# roomba.net
KiCad netlist of a schematic drawn in EAGLE
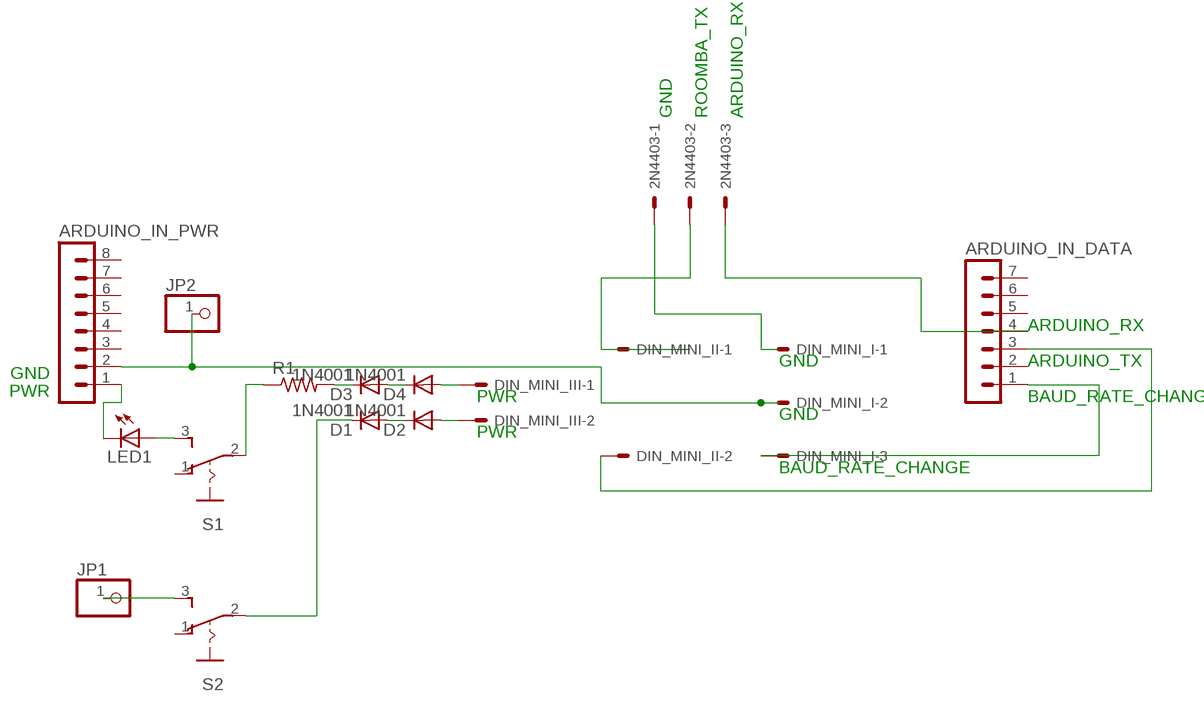
[diagram p0: schematic, sheet 1]

(export (version "E")
  (design (tool "Eeschema 10.0.6"))
  (components
    (comp (ref "2N4403")
      (value "22-23-2031")
      (footprint "eagle-import:22-23-2031")
      (fields (field (name "MF") "MOLEX"))
      (libsource (lib "eagle-import") (part "22-23-2031"))
    )
    (comp (ref "ARDUINO_IN_DATA")
      (value "MA07-1")
      (footprint "eagle-import:MA07-1")
      (libsource (lib "eagle-import") (part "MA07-1"))
    )
    (comp (ref "ARDUINO_IN_PWR")
      (value "MA08-1")
      (footprint "eagle-import:MA08-1")
      (libsource (lib "eagle-import") (part "MA08-1"))
    )
    (comp (ref "D1")
      (value "1N4001")
      (footprint "eagle-import:DO41-10")
      (libsource (lib "eagle-import") (part "1N4004"))
    )
    (comp (ref "D2")
      (value "1N4001")
      (footprint "eagle-import:DO41-10")
      (libsource (lib "eagle-import") (part "1N4004"))
    )
    (comp (ref "D3")
      (value "1N4001")
      (footprint "eagle-import:DO41-10")
      (libsource (lib "eagle-import") (part "1N4004"))
    )
    (comp (ref "D4")
      (value "1N4001")
      (footprint "eagle-import:DO41-10")
      (libsource (lib "eagle-import") (part "1N4004"))
    )
    (comp (ref "DIN_MINI_I")
      (value "22-23-2031")
      (footprint "eagle-import:22-23-2031")
      (fields (field (name "MF") "MOLEX"))
      (libsource (lib "eagle-import") (part "22-23-2031"))
    )
    (comp (ref "DIN_MINI_II")
      (value "22-23-2021")
      (footprint "eagle-import:22-23-2021")
      (fields (field (name "MF") "MOLEX"))
      (libsource (lib "eagle-import") (part "22-23-2021"))
    )
    (comp (ref "DIN_MINI_III")
      (value "22-23-2021")
      (footprint "eagle-import:22-23-2021")
      (fields (field (name "MF") "MOLEX"))
      (libsource (lib "eagle-import") (part "22-23-2021"))
    )
    (comp (ref "JP1")
      (value "PINHD-1X1")
      (footprint "eagle-import:1X01")
      (libsource (lib "eagle-import") (part "PINHD-1X1"))
    )
    (comp (ref "JP2")
      (value "PINHD-1X1")
      (footprint "eagle-import:1X01")
      (libsource (lib "eagle-import") (part "PINHD-1X1"))
    )
    (comp (ref "LED1")
      (value "LED5MM")
      (footprint "eagle-import:LED5MM")
      (libsource (lib "eagle-import") (part "LED5MM"))
    )
    (comp (ref "R1")
      (value "R-US_0207/7")
      (footprint "eagle-import:0207_7")
      (libsource (lib "eagle-import") (part "R-US_0207/7"))
    )
    (comp (ref "S1")
      (value "M251")
      (footprint "eagle-import:M251")
      (libsource (lib "eagle-import") (part "M251"))
    )
    (comp (ref "S2")
      (value "M251")
      (footprint "eagle-import:M251")
      (libsource (lib "eagle-import") (part "M251"))
    )
  )
  (nets
    (net (code "1") (name "Net-(2N4403A-S)") (class "Default")
      (node (ref "2N4403") (pin "1") (pinfunction "S_1") (pintype "passive"))
      (node (ref "DIN_MINI_I") (pin "1") (pinfunction "S_1") (pintype "passive"))
    )
    (net (code "2") (name "Net-(2N4403B-S)") (class "Default")
      (node (ref "2N4403") (pin "2") (pinfunction "S_2") (pintype "passive"))
      (node (ref "DIN_MINI_II") (pin "1") (pinfunction "S_1") (pintype "passive"))
    )
    (net (code "3") (name "Net-(2N4403C-S)") (class "Default")
      (node (ref "2N4403") (pin "3") (pinfunction "S_3") (pintype "passive"))
      (node (ref "ARDUINO_IN_DATA") (pin "4") (pinfunction "4_4") (pintype "passive"))
    )
    (net (code "4") (name "Net-(D1-PadA)") (class "Default")
      (node (ref "D1") (pin "A") (pinfunction "A_A") (pintype "passive"))
      (node (ref "D2") (pin "C") (pinfunction "C_C") (pintype "passive"))
    )
    (net (code "5") (name "Net-(D3-PadA)") (class "Default")
      (node (ref "D3") (pin "A") (pinfunction "A_A") (pintype "passive"))
      (node (ref "D4") (pin "C") (pinfunction "C_C") (pintype "passive"))
    )
    (net (code "6") (name "Net-(D3-PadC)") (class "Default")
      (node (ref "D3") (pin "C") (pinfunction "C_C") (pintype "passive"))
      (node (ref "R1") (pin "2") (pinfunction "2_2") (pintype "passive"))
    )
    (net (code "7") (name "Net-(DIN_MINI_IB-S)") (class "Default")
      (node (ref "ARDUINO_IN_PWR") (pin "2") (pinfunction "2_2") (pintype "passive"))
      (node (ref "DIN_MINI_I") (pin "2") (pinfunction "S_2") (pintype "passive"))
      (node (ref "JP2") (pin "1") (pinfunction "1_1") (pintype "passive"))
    )
    (net (code "8") (name "Net-(DIN_MINI_IC-S)") (class "Default")
      (node (ref "ARDUINO_IN_DATA") (pin "1") (pinfunction "1_1") (pintype "passive"))
      (node (ref "DIN_MINI_I") (pin "3") (pinfunction "S_3") (pintype "passive"))
    )
    (net (code "9") (name "Net-(DIN_MINI_IIB-S)") (class "Default")
      (node (ref "ARDUINO_IN_DATA") (pin "3") (pinfunction "3_3") (pintype "passive"))
      (node (ref "DIN_MINI_II") (pin "2") (pinfunction "S_2") (pintype "passive"))
    )
    (net (code "10") (name "Net-(DIN_MINI_IIIA-S)") (class "Default")
      (node (ref "D4") (pin "A") (pinfunction "A_A") (pintype "passive"))
      (node (ref "DIN_MINI_III") (pin "1") (pinfunction "S_1") (pintype "passive"))
    )
    (net (code "11") (name "Net-(DIN_MINI_IIIB-S)") (class "Default")
      (node (ref "D2") (pin "A") (pinfunction "A_A") (pintype "passive"))
      (node (ref "DIN_MINI_III") (pin "2") (pinfunction "S_2") (pintype "passive"))
    )
    (net (code "12") (name "Net-(LED1-C)") (class "Default")
      (node (ref "ARDUINO_IN_PWR") (pin "1") (pinfunction "1_1") (pintype "passive"))
      (node (ref "LED1") (pin "K") (pinfunction "C_K") (pintype "passive"))
    )
    (net (code "13") (name "Net-(S1-P)") (class "Default")
      (node (ref "R1") (pin "1") (pinfunction "1_1") (pintype "passive"))
      (node (ref "S1") (pin "2") (pinfunction "P_2") (pintype "passive"))
    )
    (net (code "14") (name "Net-(S1-S)") (class "Default")
      (node (ref "LED1") (pin "A") (pinfunction "A_A") (pintype "passive"))
      (node (ref "S1") (pin "3") (pinfunction "S_3") (pintype "passive"))
    )
    (net (code "15") (name "Net-(S2-P)") (class "Default")
      (node (ref "D1") (pin "C") (pinfunction "C_C") (pintype "passive"))
      (node (ref "S2") (pin "2") (pinfunction "P_2") (pintype "passive"))
    )
    (net (code "16") (name "Net-(S2-S)") (class "Default")
      (node (ref "JP1") (pin "1") (pinfunction "1_1") (pintype "passive"))
      (node (ref "S2") (pin "3") (pinfunction "S_3") (pintype "passive"))
    )
    (net (code "17") (name "unconnected-(ARDUINO_IN_DATA-Pad2)") (class "Default")
      (node (ref "ARDUINO_IN_DATA") (pin "2") (pinfunction "2_2") (pintype "passive"))
    )
    (net (code "18") (name "unconnected-(ARDUINO_IN_DATA-Pad5)") (class "Default")
      (node (ref "ARDUINO_IN_DATA") (pin "5") (pinfunction "5_5") (pintype "passive"))
    )
    (net (code "19") (name "unconnected-(ARDUINO_IN_DATA-Pad6)") (class "Default")
      (node (ref "ARDUINO_IN_DATA") (pin "6") (pinfunction "6_6") (pintype "passive"))
    )
    (net (code "20") (name "unconnected-(ARDUINO_IN_DATA-Pad7)") (class "Default")
      (node (ref "ARDUINO_IN_DATA") (pin "7") (pinfunction "7_7") (pintype "passive"))
    )
    (net (code "21") (name "unconnected-(ARDUINO_IN_PWR-Pad3)") (class "Default")
      (node (ref "ARDUINO_IN_PWR") (pin "3") (pinfunction "3_3") (pintype "passive"))
    )
    (net (code "22") (name "unconnected-(ARDUINO_IN_PWR-Pad4)") (class "Default")
      (node (ref "ARDUINO_IN_PWR") (pin "4") (pinfunction "4_4") (pintype "passive"))
    )
    (net (code "23") (name "unconnected-(ARDUINO_IN_PWR-Pad5)") (class "Default")
      (node (ref "ARDUINO_IN_PWR") (pin "5") (pinfunction "5_5") (pintype "passive"))
    )
    (net (code "24") (name "unconnected-(ARDUINO_IN_PWR-Pad6)") (class "Default")
      (node (ref "ARDUINO_IN_PWR") (pin "6") (pinfunction "6_6") (pintype "passive"))
    )
    (net (code "25") (name "unconnected-(ARDUINO_IN_PWR-Pad7)") (class "Default")
      (node (ref "ARDUINO_IN_PWR") (pin "7") (pinfunction "7_7") (pintype "passive"))
    )
    (net (code "26") (name "unconnected-(ARDUINO_IN_PWR-Pad8)") (class "Default")
      (node (ref "ARDUINO_IN_PWR") (pin "8") (pinfunction "8_8") (pintype "passive"))
    )
    (net (code "27") (name "unconnected-(S1-O-Pad1)") (class "Default")
      (node (ref "S1") (pin "1") (pinfunction "O_1") (pintype "passive"))
    )
    (net (code "28") (name "unconnected-(S2-O-Pad1)") (class "Default")
      (node (ref "S2") (pin "1") (pinfunction "O_1") (pintype "passive"))
    )
  )
)
